# DUAL_SIM_INTERFACE.net
KiCad netlist of a schematic drawn in Altium Designer
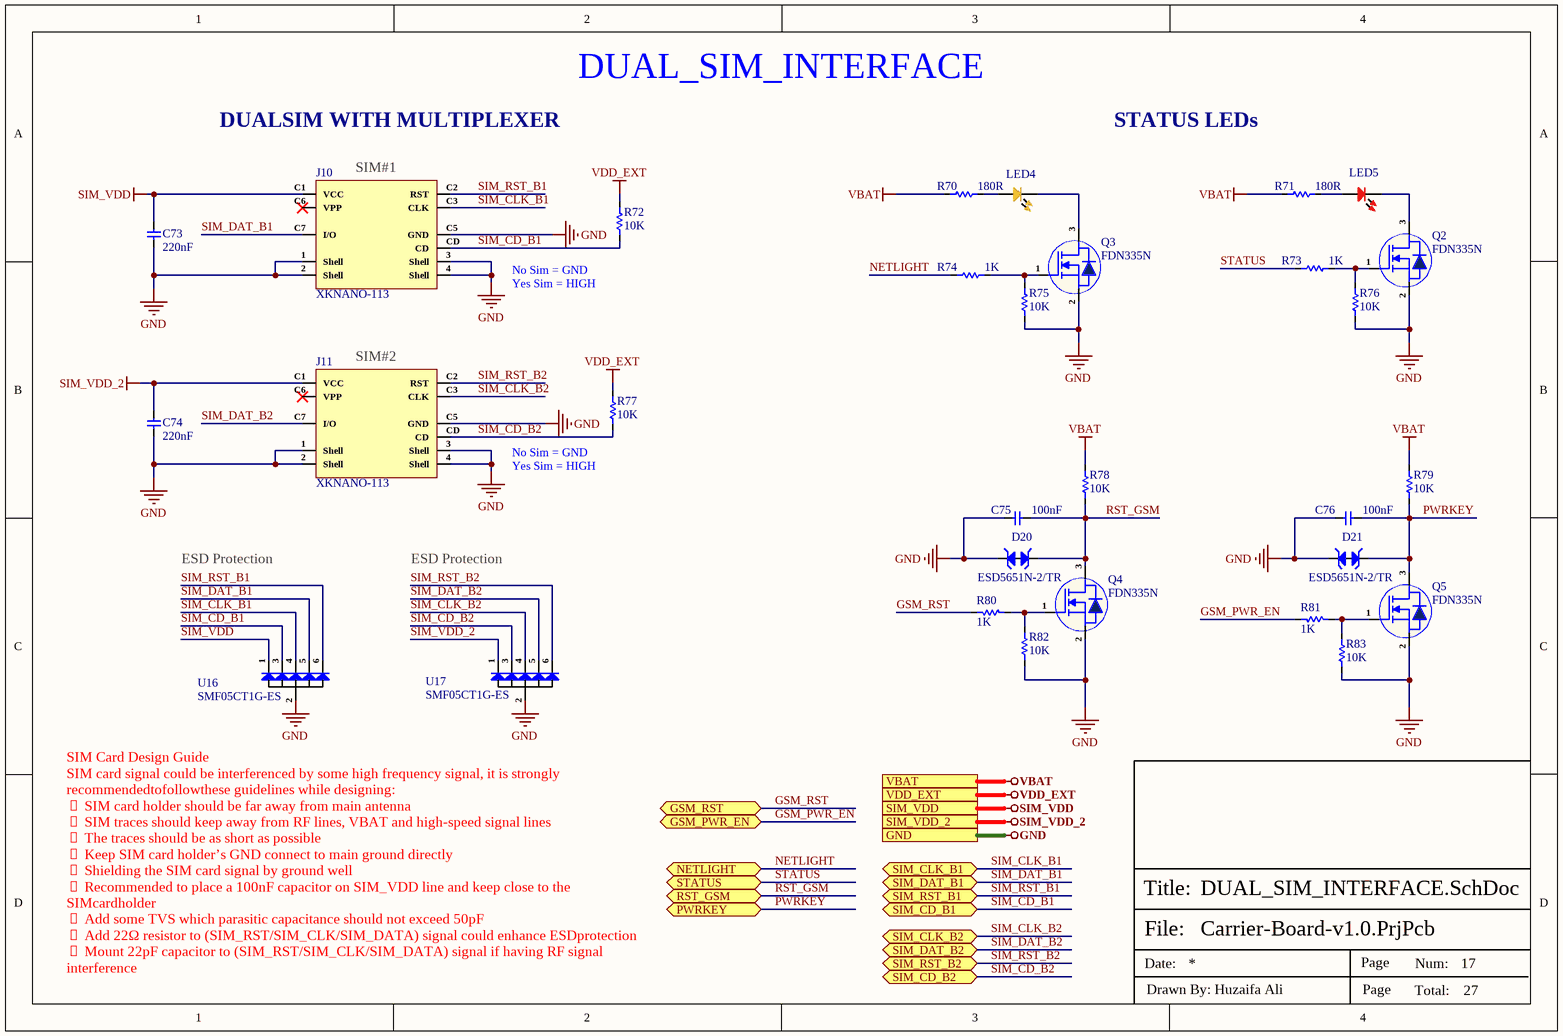
[diagram p0: DUAL_SIM_INTERFACE.SchDoc]

(export (version "E")
  (design (tool "Eeschema 10.0.6"))
  (components
    (comp (ref "C73")
      (value "220nF")
      (footprint "Cap-0402")
      (description "CAP CER 0.22UF 25V X5R 0402")
      (fields
        (field (name "MANUFACTURER") "Yageo")
        (field (name "MANUFACTURER PART NUMBER") "CC0402KRX5R8BB224")
      )
      (libsource (lib "eSpark Libraries") (part "CC0402KRX5R8BB224"))
    )
    (comp (ref "C74")
      (value "220nF")
      (footprint "Cap-0402")
      (description "CAP CER 0.22UF 25V X5R 0402")
      (fields
        (field (name "MANUFACTURER") "Yageo")
        (field (name "MANUFACTURER PART NUMBER") "CC0402KRX5R8BB224")
      )
      (libsource (lib "eSpark Libraries") (part "CC0402KRX5R8BB224"))
    )
    (comp (ref "C75")
      (value "100nF")
      (footprint "Cap-0402")
      (description "CAP CER 0.1UF 16V X5R 0402")
      (fields
        (field (name "MANUFACTURER") "Yageo")
        (field (name "MANUFACTURER PART NUMBER") "CC0402KRX5R7BB104")
      )
      (libsource (lib "eSpark Libraries") (part "CC0402KRX5R7BB104"))
    )
    (comp (ref "C76")
      (value "100nF")
      (footprint "Cap-0402")
      (description "CAP CER 0.1UF 16V X5R 0402")
      (fields
        (field (name "MANUFACTURER") "Yageo")
        (field (name "MANUFACTURER PART NUMBER") "CC0402KRX5R7BB104")
      )
      (libsource (lib "eSpark Libraries") (part "CC0402KRX5R7BB104"))
    )
    (comp (ref "D20")
      (value "ESD5651N-2/TR")
      (footprint "DFN1006-2L_")
      (description "35A@8/20us 15V 4.5V@Max DFN1006-2L Electrostatic and Surge Protection (TVS/ESD) ROHS")
      (fields
        (field (name "MANUFACTURER") "WILLSEMI(Will Semicon)")
        (field (name "LCSC PART NUMBER") "C239784")
      )
      (libsource (lib "eSpark Libraries") (part "ESD5651N-2/TR"))
    )
    (comp (ref "D21")
      (value "ESD5651N-2/TR")
      (footprint "DFN1006-2L_")
      (description "35A@8/20us 15V 4.5V@Max DFN1006-2L Electrostatic and Surge Protection (TVS/ESD) ROHS")
      (fields
        (field (name "MANUFACTURER") "WILLSEMI(Will Semicon)")
        (field (name "LCSC PART NUMBER") "C239784")
      )
      (libsource (lib "eSpark Libraries") (part "ESD5651N-2/TR"))
    )
    (comp (ref "J10")
      (value "XKNANO-113")
      (footprint "XKNANO-113")
      (fields (field (name "MANUFACTURER") "XKB Connectivity") (field (name "LCSC PART NUMBER") "C381071"))
      (libsource (lib "eSpark Libraries") (part "XKNANO-113"))
    )
    (comp (ref "J11")
      (value "XKNANO-113")
      (footprint "XKNANO-113")
      (fields (field (name "MANUFACTURER") "XKB Connectivity") (field (name "LCSC PART NUMBER") "C381071"))
      (libsource (lib "eSpark Libraries") (part "XKNANO-113"))
    )
    (comp (ref "LED4")
      (value "Yellow")
      (footprint "LED-0402")
      (description "LED YELLOW CLEAR CHIP SMD")
      (fields (field (name "MANUFACTURER") "SunLED") (field (name "MANUFACTURER PART NUMBER") "XZMYK68W-2"))
      (libsource (lib "eSpark Libraries") (part "XZMYK68W-2"))
    )
    (comp (ref "LED5")
      (value "Red")
      (footprint "LED-0402")
      (description "LED RED CLEAR CHIP SMD")
      (fields (field (name "MANUFACTURER") "SunLED") (field (name "MANUFACTURER PART NUMBER") "XZMDK68W-2"))
      (libsource (lib "eSpark Libraries") (part "XZMDK68W-2"))
    )
    (comp (ref "Q2")
      (value "FDN335N")
      (footprint "SOT-23")
      (description "SOT-23 MOSFETs ROHS")
      (fields (field (name "MANUFACTURER") "TECH PUBLIC") (field (name "LCSC PART NUMBER") "C5123904"))
      (libsource (lib "eSpark Libraries") (part "FDN335N"))
    )
    (comp (ref "Q3")
      (value "FDN335N")
      (footprint "SOT-23")
      (description "SOT-23 MOSFETs ROHS")
      (fields (field (name "MANUFACTURER") "TECH PUBLIC") (field (name "LCSC PART NUMBER") "C5123904"))
      (libsource (lib "eSpark Libraries") (part "FDN335N"))
    )
    (comp (ref "Q4")
      (value "FDN335N")
      (footprint "SOT-23")
      (description "SOT-23 MOSFETs ROHS")
      (fields (field (name "MANUFACTURER") "TECH PUBLIC") (field (name "LCSC PART NUMBER") "C5123904"))
      (libsource (lib "eSpark Libraries") (part "FDN335N"))
    )
    (comp (ref "Q5")
      (value "FDN335N")
      (footprint "SOT-23")
      (description "SOT-23 MOSFETs ROHS")
      (fields (field (name "MANUFACTURER") "TECH PUBLIC") (field (name "LCSC PART NUMBER") "C5123904"))
      (libsource (lib "eSpark Libraries") (part "FDN335N"))
    )
    (comp (ref "R70")
      (value "180R")
      (footprint "Res-0603")
      (description "RES 180 OHM 1% 1/10W 0603")
      (fields
        (field (name "MANUFACTURER") "Yageo")
        (field (name "MANUFACTURER PART NUMBER") "RC0603FR-07180RL")
      )
      (libsource (lib "eSpark Libraries") (part "RC0603FR-07180RL"))
    )
    (comp (ref "R71")
      (value "180R")
      (footprint "Res-0603")
      (description "RES 180 OHM 1% 1/10W 0603")
      (fields
        (field (name "MANUFACTURER") "Yageo")
        (field (name "MANUFACTURER PART NUMBER") "RC0603FR-07180RL")
      )
      (libsource (lib "eSpark Libraries") (part "RC0603FR-07180RL"))
    )
    (comp (ref "R72")
      (value "10K")
      (footprint "Res-0402")
      (description "RES 10K OHM 1% 1/16W 0402")
      (fields
        (field (name "MANUFACTURER") "Yageo")
        (field (name "MANUFACTURER PART NUMBER") "RC0402FR-0710KL")
      )
      (libsource (lib "eSpark Libraries") (part "RC0402FR-0710KL"))
    )
    (comp (ref "R73")
      (value "1K")
      (footprint "Res-0402")
      (description "RES 1K OHM 1% 1/16W 0402")
      (fields
        (field (name "MANUFACTURER") "Yageo")
        (field (name "MANUFACTURER PART NUMBER") "RC0402FR-071KL")
      )
      (libsource (lib "eSpark Libraries") (part "RC0402FR-071KL"))
    )
    (comp (ref "R74")
      (value "1K")
      (footprint "Res-0402")
      (description "RES 1K OHM 1% 1/16W 0402")
      (fields
        (field (name "MANUFACTURER") "Yageo")
        (field (name "MANUFACTURER PART NUMBER") "RC0402FR-071KL")
      )
      (libsource (lib "eSpark Libraries") (part "RC0402FR-071KL"))
    )
    (comp (ref "R75")
      (value "10K")
      (footprint "Res-0402")
      (description "RES 10K OHM 1% 1/16W 0402")
      (fields
        (field (name "MANUFACTURER") "Yageo")
        (field (name "MANUFACTURER PART NUMBER") "RC0402FR-0710KL")
      )
      (libsource (lib "eSpark Libraries") (part "RC0402FR-0710KL"))
    )
    (comp (ref "R76")
      (value "10K")
      (footprint "Res-0402")
      (description "RES 10K OHM 1% 1/16W 0402")
      (fields
        (field (name "MANUFACTURER") "Yageo")
        (field (name "MANUFACTURER PART NUMBER") "RC0402FR-0710KL")
      )
      (libsource (lib "eSpark Libraries") (part "RC0402FR-0710KL"))
    )
    (comp (ref "R77")
      (value "10K")
      (footprint "Res-0402")
      (description "RES 10K OHM 1% 1/16W 0402")
      (fields
        (field (name "MANUFACTURER") "Yageo")
        (field (name "MANUFACTURER PART NUMBER") "RC0402FR-0710KL")
      )
      (libsource (lib "eSpark Libraries") (part "RC0402FR-0710KL"))
    )
    (comp (ref "R78")
      (value "10K")
      (footprint "Res-0402")
      (description "RES 10K OHM 1% 1/16W 0402")
      (fields
        (field (name "MANUFACTURER") "Yageo")
        (field (name "MANUFACTURER PART NUMBER") "RC0402FR-0710KL")
      )
      (libsource (lib "eSpark Libraries") (part "RC0402FR-0710KL"))
    )
    (comp (ref "R79")
      (value "10K")
      (footprint "Res-0402")
      (description "RES 10K OHM 1% 1/16W 0402")
      (fields
        (field (name "MANUFACTURER") "Yageo")
        (field (name "MANUFACTURER PART NUMBER") "RC0402FR-0710KL")
      )
      (libsource (lib "eSpark Libraries") (part "RC0402FR-0710KL"))
    )
    (comp (ref "R80")
      (value "1K")
      (footprint "Res-0402")
      (description "RES 1K OHM 1% 1/16W 0402")
      (fields
        (field (name "MANUFACTURER") "Yageo")
        (field (name "MANUFACTURER PART NUMBER") "RC0402FR-071KL")
      )
      (libsource (lib "eSpark Libraries") (part "RC0402FR-071KL"))
    )
    (comp (ref "R81")
      (value "1K")
      (footprint "Res-0402")
      (description "RES 1K OHM 1% 1/16W 0402")
      (fields
        (field (name "MANUFACTURER") "Yageo")
        (field (name "MANUFACTURER PART NUMBER") "RC0402FR-071KL")
      )
      (libsource (lib "eSpark Libraries") (part "RC0402FR-071KL"))
    )
    (comp (ref "R82")
      (value "10K")
      (footprint "Res-0402")
      (description "RES 10K OHM 1% 1/16W 0402")
      (fields
        (field (name "MANUFACTURER") "Yageo")
        (field (name "MANUFACTURER PART NUMBER") "RC0402FR-0710KL")
      )
      (libsource (lib "eSpark Libraries") (part "RC0402FR-0710KL"))
    )
    (comp (ref "R83")
      (value "10K")
      (footprint "Res-0402")
      (description "RES 10K OHM 1% 1/16W 0402")
      (fields
        (field (name "MANUFACTURER") "Yageo")
        (field (name "MANUFACTURER PART NUMBER") "RC0402FR-0710KL")
      )
      (libsource (lib "eSpark Libraries") (part "RC0402FR-0710KL"))
    )
    (comp (ref "U16")
      (value "SMF05CT1G-ES")
      (footprint "SOT-363")
      (description "15V 5 Unidirectional 5V SOT-363 ESD Protection Devices ROHS")
      (fields (field (name "MANUFACTURER") "ElecSuper") (field (name "LCSC PART NUMBER") "C5180312"))
      (libsource (lib "eSpark Libraries") (part "SMF05CT1G-ES"))
    )
    (comp (ref "U17")
      (value "SMF05CT1G-ES")
      (footprint "SOT-363")
      (description "15V 5 Unidirectional 5V SOT-363 ESD Protection Devices ROHS")
      (fields (field (name "MANUFACTURER") "ElecSuper") (field (name "LCSC PART NUMBER") "C5180312"))
      (libsource (lib "eSpark Libraries") (part "SMF05CT1G-ES"))
    )
  )
  (nets
    (net (code "1") (name "/GSM_PWR_EN") (class "Default")
      (node (ref "R81") (pin "2") (pinfunction "2_2") (pintype "passive"))
    )
    (net (code "2") (name "/GSM_RST") (class "Default")
      (node (ref "R80") (pin "1") (pinfunction "1_1") (pintype "passive"))
    )
    (net (code "3") (name "/NETLIGHT") (class "Default")
      (node (ref "R74") (pin "1") (pinfunction "1_1") (pintype "passive"))
    )
    (net (code "4") (name "/PWRKEY") (class "Default")
      (node (ref "C76") (pin "2") (pinfunction "2_2") (pintype "passive"))
      (node (ref "D21") (pin "2") (pinfunction "K_2") (pintype "passive"))
      (node (ref "Q5") (pin "3") (pinfunction "D_3") (pintype "passive"))
      (node (ref "R79") (pin "1") (pinfunction "1_1") (pintype "passive"))
    )
    (net (code "5") (name "/RST_GSM") (class "Default")
      (node (ref "C75") (pin "2") (pinfunction "2_2") (pintype "passive"))
      (node (ref "D20") (pin "2") (pinfunction "K_2") (pintype "passive"))
      (node (ref "Q4") (pin "3") (pinfunction "D_3") (pintype "passive"))
      (node (ref "R78") (pin "1") (pinfunction "1_1") (pintype "passive"))
    )
    (net (code "6") (name "/SIM_CD_B1") (class "Default")
      (node (ref "J10") (pin "CD") (pinfunction "CD_CD") (pintype "passive"))
      (node (ref "R72") (pin "1") (pinfunction "1_1") (pintype "passive"))
      (node (ref "U16") (pin "3") (pinfunction "IO2_3") (pintype "passive"))
    )
    (net (code "7") (name "/SIM_CD_B2") (class "Default")
      (node (ref "J11") (pin "CD") (pinfunction "CD_CD") (pintype "passive"))
      (node (ref "R77") (pin "1") (pinfunction "1_1") (pintype "passive"))
      (node (ref "U17") (pin "3") (pinfunction "IO2_3") (pintype "passive"))
    )
    (net (code "8") (name "/SIM_CLK_B1") (class "Default")
      (node (ref "J10") (pin "C3") (pinfunction "CLK_C3") (pintype "passive"))
      (node (ref "U16") (pin "4") (pinfunction "IO3_4") (pintype "passive"))
    )
    (net (code "9") (name "/SIM_CLK_B2") (class "Default")
      (node (ref "J11") (pin "C3") (pinfunction "CLK_C3") (pintype "passive"))
      (node (ref "U17") (pin "4") (pinfunction "IO3_4") (pintype "passive"))
    )
    (net (code "10") (name "/SIM_DAT_B1") (class "Default")
      (node (ref "J10") (pin "C7") (pinfunction "I/O_C7") (pintype "passive"))
      (node (ref "U16") (pin "5") (pinfunction "IO4_5") (pintype "passive"))
    )
    (net (code "11") (name "/SIM_DAT_B2") (class "Default")
      (node (ref "J11") (pin "C7") (pinfunction "I/O_C7") (pintype "passive"))
      (node (ref "U17") (pin "5") (pinfunction "IO4_5") (pintype "passive"))
    )
    (net (code "12") (name "/SIM_RST_B1") (class "Default")
      (node (ref "J10") (pin "C2") (pinfunction "RST_C2") (pintype "passive"))
      (node (ref "U16") (pin "6") (pinfunction "IO5_6") (pintype "passive"))
    )
    (net (code "13") (name "/SIM_RST_B2") (class "Default")
      (node (ref "J11") (pin "C2") (pinfunction "RST_C2") (pintype "passive"))
      (node (ref "U17") (pin "6") (pinfunction "IO5_6") (pintype "passive"))
    )
    (net (code "14") (name "/STATUS") (class "Default")
      (node (ref "R73") (pin "1") (pinfunction "1_1") (pintype "passive"))
    )
    (net (code "15") (name "GND") (class "Default")
      (node (ref "C73") (pin "2") (pinfunction "2_2") (pintype "passive"))
      (node (ref "C74") (pin "2") (pinfunction "2_2") (pintype "passive"))
      (node (ref "C75") (pin "1") (pinfunction "1_1") (pintype "passive"))
      (node (ref "C76") (pin "1") (pinfunction "1_1") (pintype "passive"))
      (node (ref "D20") (pin "1") (pinfunction "K_1") (pintype "passive"))
      (node (ref "D21") (pin "1") (pinfunction "K_1") (pintype "passive"))
      (node (ref "J10") (pin "1") (pinfunction "Shell_1") (pintype "passive"))
      (node (ref "J10") (pin "2") (pinfunction "Shell_2") (pintype "passive"))
      (node (ref "J10") (pin "3") (pinfunction "Shell_3") (pintype "passive"))
      (node (ref "J10") (pin "4") (pinfunction "Shell_4") (pintype "passive"))
      (node (ref "J10") (pin "C5") (pinfunction "GND_C5") (pintype "passive"))
      (node (ref "J11") (pin "1") (pinfunction "Shell_1") (pintype "passive"))
      (node (ref "J11") (pin "2") (pinfunction "Shell_2") (pintype "passive"))
      (node (ref "J11") (pin "3") (pinfunction "Shell_3") (pintype "passive"))
      (node (ref "J11") (pin "4") (pinfunction "Shell_4") (pintype "passive"))
      (node (ref "J11") (pin "C5") (pinfunction "GND_C5") (pintype "passive"))
      (node (ref "Q2") (pin "2") (pinfunction "S_2") (pintype "passive"))
      (node (ref "Q3") (pin "2") (pinfunction "S_2") (pintype "passive"))
      (node (ref "Q4") (pin "2") (pinfunction "S_2") (pintype "passive"))
      (node (ref "Q5") (pin "2") (pinfunction "S_2") (pintype "passive"))
      (node (ref "R75") (pin "1") (pinfunction "1_1") (pintype "passive"))
      (node (ref "R76") (pin "1") (pinfunction "1_1") (pintype "passive"))
      (node (ref "R82") (pin "1") (pinfunction "1_1") (pintype "passive"))
      (node (ref "R83") (pin "1") (pinfunction "1_1") (pintype "passive"))
      (node (ref "U16") (pin "2") (pinfunction "A_2") (pintype "passive"))
      (node (ref "U17") (pin "2") (pinfunction "A_2") (pintype "passive"))
    )
    (net (code "16") (name "Net-(LED4-Pad1)") (class "Default")
      (node (ref "LED4") (pin "1") (pinfunction "1_1") (pintype "passive"))
      (node (ref "R70") (pin "1") (pinfunction "1_1") (pintype "passive"))
    )
    (net (code "17") (name "Net-(LED5-Pad1)") (class "Default")
      (node (ref "LED5") (pin "1") (pinfunction "1_1") (pintype "passive"))
      (node (ref "R71") (pin "1") (pinfunction "1_1") (pintype "passive"))
    )
    (net (code "18") (name "Net-(Q2-D)") (class "Default")
      (node (ref "LED5") (pin "2") (pinfunction "2_2") (pintype "passive"))
      (node (ref "Q2") (pin "3") (pinfunction "D_3") (pintype "passive"))
    )
    (net (code "19") (name "Net-(Q2-G)") (class "Default")
      (node (ref "Q2") (pin "1") (pinfunction "G_1") (pintype "passive"))
      (node (ref "R73") (pin "2") (pinfunction "2_2") (pintype "passive"))
      (node (ref "R76") (pin "2") (pinfunction "2_2") (pintype "passive"))
    )
    (net (code "20") (name "Net-(Q3-D)") (class "Default")
      (node (ref "LED4") (pin "2") (pinfunction "2_2") (pintype "passive"))
      (node (ref "Q3") (pin "3") (pinfunction "D_3") (pintype "passive"))
    )
    (net (code "21") (name "Net-(Q3-G)") (class "Default")
      (node (ref "Q3") (pin "1") (pinfunction "G_1") (pintype "passive"))
      (node (ref "R74") (pin "2") (pinfunction "2_2") (pintype "passive"))
      (node (ref "R75") (pin "2") (pinfunction "2_2") (pintype "passive"))
    )
    (net (code "22") (name "Net-(Q4-G)") (class "Default")
      (node (ref "Q4") (pin "1") (pinfunction "G_1") (pintype "passive"))
      (node (ref "R80") (pin "2") (pinfunction "2_2") (pintype "passive"))
      (node (ref "R82") (pin "2") (pinfunction "2_2") (pintype "passive"))
    )
    (net (code "23") (name "Net-(Q5-G)") (class "Default")
      (node (ref "Q5") (pin "1") (pinfunction "G_1") (pintype "passive"))
      (node (ref "R81") (pin "1") (pinfunction "1_1") (pintype "passive"))
      (node (ref "R83") (pin "2") (pinfunction "2_2") (pintype "passive"))
    )
    (net (code "24") (name "SIM_VDD") (class "Default")
      (node (ref "C73") (pin "1") (pinfunction "1_1") (pintype "passive"))
      (node (ref "J10") (pin "C1") (pinfunction "VCC_C1") (pintype "passive"))
      (node (ref "U16") (pin "1") (pinfunction "IO1_1") (pintype "passive"))
    )
    (net (code "25") (name "SIM_VDD_2") (class "Default")
      (node (ref "C74") (pin "1") (pinfunction "1_1") (pintype "passive"))
      (node (ref "J11") (pin "C1") (pinfunction "VCC_C1") (pintype "passive"))
      (node (ref "U17") (pin "1") (pinfunction "IO1_1") (pintype "passive"))
    )
    (net (code "26") (name "VBAT") (class "Default")
      (node (ref "R70") (pin "2") (pinfunction "2_2") (pintype "passive"))
      (node (ref "R71") (pin "2") (pinfunction "2_2") (pintype "passive"))
      (node (ref "R78") (pin "2") (pinfunction "2_2") (pintype "passive"))
      (node (ref "R79") (pin "2") (pinfunction "2_2") (pintype "passive"))
    )
    (net (code "27") (name "VDD_EXT") (class "Default")
      (node (ref "R72") (pin "2") (pinfunction "2_2") (pintype "passive"))
      (node (ref "R77") (pin "2") (pinfunction "2_2") (pintype "passive"))
    )
    (net (code "28") (name "unconnected-(J10-VPP-PadC6)") (class "Default")
      (node (ref "J10") (pin "C6") (pinfunction "VPP_C6") (pintype "passive+no_connect"))
    )
    (net (code "29") (name "unconnected-(J11-VPP-PadC6)") (class "Default")
      (node (ref "J11") (pin "C6") (pinfunction "VPP_C6") (pintype "passive+no_connect"))
    )
  )
)
